# PR9025.net
KiCad netlist of a schematic drawn in EAGLE
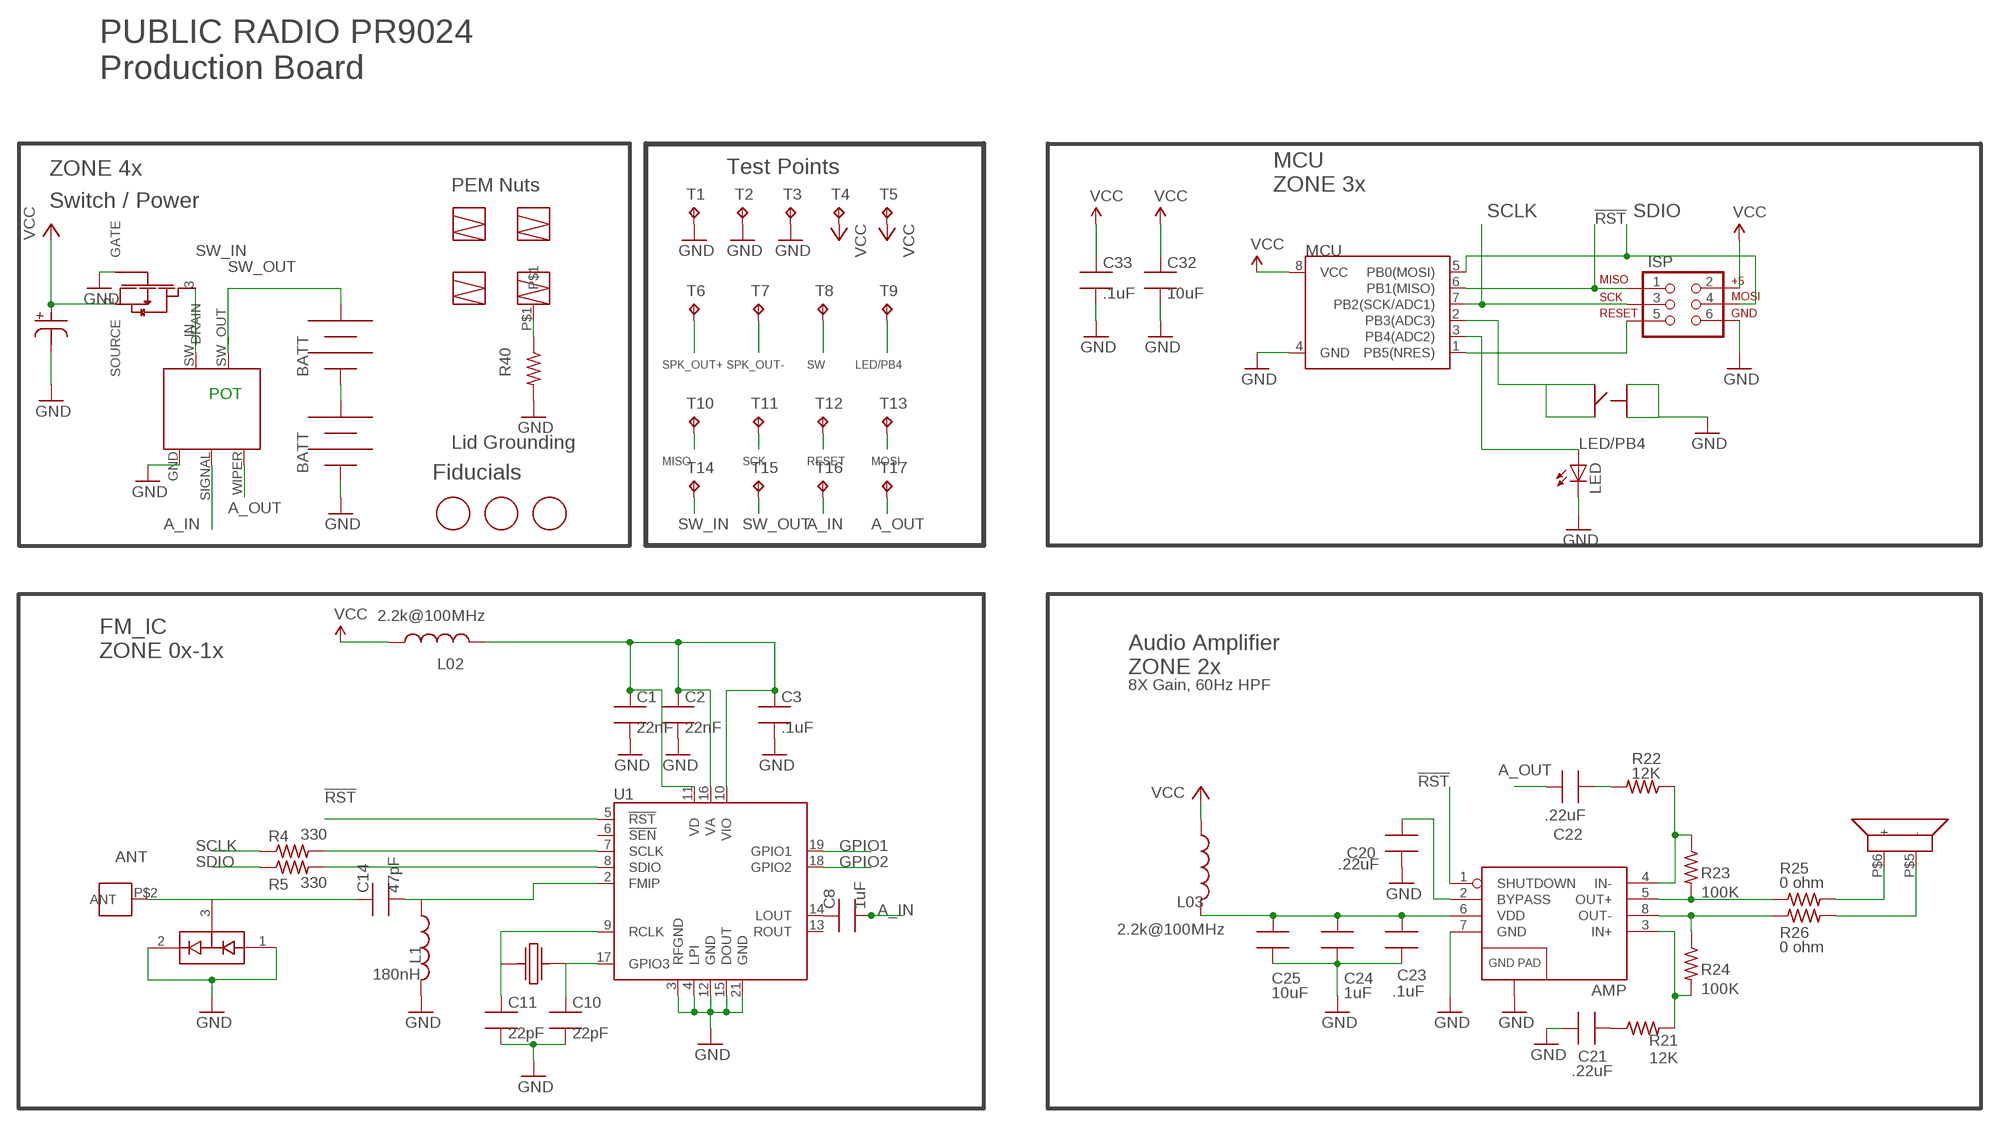
[diagram p0: schematic, sheet 1]

(export (version "E")
  (design (tool "Eeschema 10.0.6"))
  (components
    (comp (ref "AMP")
      (value "TPA6203A1")
      (footprint "eagle-import:8-MSOP")
      (libsource (lib "eagle-import") (part "TPA6203A1"))
    )
    (comp (ref "ANT_MOUNT")
      (value "DNP")
      (footprint "eagle-import:PEM_M3")
      (libsource (lib "eagle-import") (part "M3_PEMNUT"))
    )
    (comp (ref "C1")
      (value "22nF")
      (footprint "eagle-import:0603_CPL")
      (fields
        (field (name "MFG_PN") "CL10B223KB8NNNC")
        (field (name "TOL") "10%")
        (field (name "VOLTAGE") "16V")
      )
      (libsource (lib "eagle-import") (part "C_SMT_0603_CPL"))
    )
    (comp (ref "C2")
      (value "22nF")
      (footprint "eagle-import:0603_CPL")
      (fields
        (field (name "MFG_PN") "CL10B223KB8NNNC")
        (field (name "TOL") "10%")
        (field (name "VOLTAGE") "16V")
      )
      (libsource (lib "eagle-import") (part "C_SMT_0603_CPL"))
    )
    (comp (ref "C3")
      (value ".1uF")
      (footprint "eagle-import:0603_CPL")
      (fields
        (field (name "MFG_PN") "CL10B104KB8SFNC")
        (field (name "TOL") "10%")
        (field (name "VOLTAGE") "16V")
      )
      (libsource (lib "eagle-import") (part "C_SMT_0603_CPL"))
    )
    (comp (ref "C8")
      (value "1uF")
      (footprint "eagle-import:0603_CPL")
      (fields
        (field (name "MFG_PN") "CL10B105KP8NNNC")
        (field (name "TOL") "10%")
        (field (name "VOLTAGE") "10V")
      )
      (libsource (lib "eagle-import") (part "C_SMT_0603_CPL"))
    )
    (comp (ref "C10")
      (value "22pF")
      (footprint "eagle-import:0603_CPL")
      (fields
        (field (name "MFG_PN") "C1608C0G1H220J080AA")
        (field (name "TOL") "5%")
        (field (name "VOLTAGE") "50V")
      )
      (libsource (lib "eagle-import") (part "C_SMT_0603_CPL"))
    )
    (comp (ref "C11")
      (value "22pF")
      (footprint "eagle-import:0603_CPL")
      (fields
        (field (name "MFG_PN") "C1608C0G1H220J080AA")
        (field (name "TOL") "5%")
        (field (name "VOLTAGE") "50V")
      )
      (libsource (lib "eagle-import") (part "C_SMT_0603_CPL"))
    )
    (comp (ref "C14")
      (value "47pF")
      (footprint "eagle-import:0603_CPL")
      (fields
        (field (name "MFG_PN") "CL10C470JB8NCNC")
        (field (name "TOL") "5%")
        (field (name "VOLTAGE") "50V")
      )
      (libsource (lib "eagle-import") (part "C_SMT_0603_CPL"))
    )
    (comp (ref "C20")
      (value ".22uF")
      (footprint "eagle-import:0603_CPL")
      (fields
        (field (name "MFG_PN") "C1608X7R1C224K080AC")
        (field (name "TOL") "10%")
        (field (name "VOLTAGE") "16V")
      )
      (libsource (lib "eagle-import") (part "C_SMT_0603_CPL"))
    )
    (comp (ref "C21")
      (value ".22uF")
      (footprint "eagle-import:0603_CPL")
      (fields
        (field (name "MFG_PN") "C1608X7R1C224K080AC")
        (field (name "TOL") "10%")
        (field (name "VOLTAGE") "16V")
      )
      (libsource (lib "eagle-import") (part "C_SMT_0603_CPL"))
    )
    (comp (ref "C22")
      (value ".22uF")
      (footprint "eagle-import:0603_CPL")
      (fields
        (field (name "MFG_PN") "C1608X7R1C224K080AC")
        (field (name "TOL") "10%")
        (field (name "VOLTAGE") "16V")
      )
      (libsource (lib "eagle-import") (part "C_SMT_0603_CPL"))
    )
    (comp (ref "C23")
      (value ".1uF")
      (footprint "eagle-import:0603_CPL")
      (fields
        (field (name "MFG_PN") "CL10B104KB8SFNC")
        (field (name "TOL") "10%")
        (field (name "VOLTAGE") "16V")
      )
      (libsource (lib "eagle-import") (part "C_SMT_0603_CPL"))
    )
    (comp (ref "C24")
      (value "1uF")
      (footprint "eagle-import:0603_CPL")
      (fields
        (field (name "MFG_PN") "CL10B105KP8NNNC")
        (field (name "TOL") "10%")
        (field (name "VOLTAGE") "10V")
      )
      (libsource (lib "eagle-import") (part "C_SMT_0603_CPL"))
    )
    (comp (ref "C25")
      (value "10uF")
      (footprint "eagle-import:0603_CPL")
      (fields
        (field (name "MFG_PN") "CL10A106MQ8NNNC")
        (field (name "TOL") "20%")
        (field (name "VOLTAGE") "6.3V")
      )
      (libsource (lib "eagle-import") (part "C_SMT_0603_CPL"))
    )
    (comp (ref "C32")
      (value "10uF")
      (footprint "eagle-import:0603_CPL")
      (fields
        (field (name "MFG_PN") "CL10A106MQ8NNNC")
        (field (name "TOL") "20%")
        (field (name "VOLTAGE") "6.3V")
      )
      (libsource (lib "eagle-import") (part "C_SMT_0603_CPL"))
    )
    (comp (ref "C33")
      (value ".1uF")
      (footprint "eagle-import:0603_CPL")
      (fields
        (field (name "MFG_PN") "CL10B104KB8SFNC")
        (field (name "TOL") "10%")
        (field (name "VOLTAGE") "16V")
      )
      (libsource (lib "eagle-import") (part "C_SMT_0603_CPL"))
    )
    (comp (ref "C40")
      (value "220uF")
      (footprint "eagle-import:NICHICON_UD_63")
      (fields (field (name "TOL") "20%") (field (name "VOLTAGE") "16V"))
      (libsource (lib "eagle-import") (part "NICHICON_SERIESUD"))
    )
    (comp (ref "D1")
      (value "BAV99")
      (footprint "eagle-import:SOT23_CPL")
      (fields (field (name "MFG_PN") "BAV99,215"))
      (libsource (lib "eagle-import") (part "BAV99"))
    )
    (comp (ref "FET1")
      (value "AO3435")
      (footprint "eagle-import:SOT23_CPL")
      (fields (field (name "MFG_PN") "AO3435"))
      (libsource (lib "eagle-import") (part "AO3435"))
    )
    (comp (ref "ISP")
      (value "AVR_SPI_PRG_6NS")
      (footprint "eagle-import:2X3-NS")
      (libsource (lib "eagle-import") (part "AVR_SPI_PRG_6NS"))
    )
    (comp (ref "JP5")
      (value "BK-92_MPD_AA_BATT_CLIP")
      (footprint "eagle-import:BK92_AA_BATT")
      (fields (field (name "MFG_PN") "2 of BK92 - supplied by CL Labs"))
      (libsource (lib "eagle-import") (part "BK-92_MPD_AA_BATT_CLIP"))
    )
    (comp (ref "JP6")
      (value "BK-92_MPD_AA_BATT_CLIP")
      (footprint "eagle-import:BK92_AA_BATT")
      (fields (field (name "MFG_PN") "2 of BK92 - supplied by CL Labs"))
      (libsource (lib "eagle-import") (part "BK-92_MPD_AA_BATT_CLIP"))
    )
    (comp (ref "L1")
      (value "180nH")
      (footprint "eagle-import:0805_ADAFRUIT")
      (fields
        (field (name "CURRENT") "400mA")
        (field (name "DCR") "640m")
        (field (name "MFG_PN") "AISC-0805-R18J-T")
        (field (name "TOL") "5%")
      )
      (libsource (lib "eagle-import") (part "L_SMT_0805_ADAFRUIT"))
    )
    (comp (ref "L02")
      (value "2.2k@100MHz")
      (footprint "eagle-import:0603_CPL")
      (fields
        (field (name "CURRENT") "150mA")
        (field (name "DCR") "2.3")
        (field (name "MFG_PN") "HZ0603A222R-10")
      )
      (libsource (lib "eagle-import") (part "L_SMT_0603_CPL"))
    )
    (comp (ref "L03")
      (value "2.2k@100MHz")
      (footprint "eagle-import:0603_CPL")
      (fields
        (field (name "CURRENT") "150mA")
        (field (name "DCR") "2.3")
        (field (name "MFG_PN") "HZ0603A222R-10")
      )
      (libsource (lib "eagle-import") (part "L_SMT_0603_CPL"))
    )
    (comp (ref "LED")
      (value "HSMC-C265_REVERSE_MOUNT_LED")
      (footprint "eagle-import:HSMC-C265_REVERSE_MOUN_LED")
      (libsource (lib "eagle-import") (part "HSMC-C265_REVERSE_MOUNT_LED"))
    )
    (comp (ref "MARK1")
      (value "FIDUCIAL")
      (footprint "eagle-import:FIDUCIAL_1MM")
      (libsource (lib "eagle-import") (part "FIDUCIAL"))
    )
    (comp (ref "MARK2")
      (value "FIDUCIAL")
      (footprint "eagle-import:FIDUCIAL_1MM")
      (libsource (lib "eagle-import") (part "FIDUCIAL"))
    )
    (comp (ref "MARK3")
      (value "FIDUCIAL")
      (footprint "eagle-import:FIDUCIAL_1MM")
      (libsource (lib "eagle-import") (part "FIDUCIAL"))
    )
    (comp (ref "MCU")
      (value "ATTINY45TINY45-20-SMT")
      (footprint "eagle-import:8-SOIC")
      (libsource (lib "eagle-import") (part "ATTINY45TINY45-20-SMT"))
    )
    (comp (ref "R1")
      (value "VOLUME_POT")
      (footprint "eagle-import:H17112NS_A10K_L20F-002")
      (libsource (lib "eagle-import") (part "VOLUME_POT"))
    )
    (comp (ref "R4")
      (value "330")
      (footprint "eagle-import:0603_CPL")
      (fields (field (name "MFG_PN") "MCR03ERTJ331") (field (name "POWER") "1/10W") (field (name "TOL") "5%"))
      (libsource (lib "eagle-import") (part "R_SMT_R0603_CPL"))
    )
    (comp (ref "R5")
      (value "330")
      (footprint "eagle-import:0603_CPL")
      (fields (field (name "MFG_PN") "MCR03ERTJ331") (field (name "POWER") "1/10W") (field (name "TOL") "5%"))
      (libsource (lib "eagle-import") (part "R_SMT_R0603_CPL"))
    )
    (comp (ref "R21")
      (value "12K")
      (footprint "eagle-import:0603_CPL")
      (fields
        (field (name "MFG_PN") "RC0603FR-0712KL")
        (field (name "POWER") "1/10W")
        (field (name "TOL") "1%")
      )
      (libsource (lib "eagle-import") (part "R_SMT_R0603_CPL"))
    )
    (comp (ref "R22")
      (value "12K")
      (footprint "eagle-import:0603_CPL")
      (fields
        (field (name "MFG_PN") "RC0603FR-0712KL")
        (field (name "POWER") "1/10W")
        (field (name "TOL") "1%")
      )
      (libsource (lib "eagle-import") (part "R_SMT_R0603_CPL"))
    )
    (comp (ref "R23")
      (value "100K")
      (footprint "eagle-import:0603_CPL")
      (fields
        (field (name "MFG_PN") "ERJ-3EKF1003V")
        (field (name "POWER") "1/10W")
        (field (name "TOL") "1%")
      )
      (libsource (lib "eagle-import") (part "R_SMT_R0603_CPL"))
    )
    (comp (ref "R24")
      (value "100K")
      (footprint "eagle-import:0603_CPL")
      (fields
        (field (name "MFG_PN") "ERJ-3EKF1003V")
        (field (name "POWER") "1/10W")
        (field (name "TOL") "1%")
      )
      (libsource (lib "eagle-import") (part "R_SMT_R0603_CPL"))
    )
    (comp (ref "R25")
      (value "0 ohm")
      (footprint "eagle-import:0805_ADAFRUIT")
      (fields (field (name "MFG_PN") "ERJ-6GEY0R00V "))
      (libsource (lib "eagle-import") (part "R_SMT_0805_ADAFRUIT"))
    )
    (comp (ref "R26")
      (value "0 ohm")
      (footprint "eagle-import:0805_ADAFRUIT")
      (fields (field (name "MFG_PN") "ERJ-6GEY0R00V "))
      (libsource (lib "eagle-import") (part "R_SMT_0805_ADAFRUIT"))
    )
    (comp (ref "R40")
      (value "DNP")
      (footprint "eagle-import:0603_CPL")
      (fields (field (name "MFG_PN") "ERJ-3GEY0R00V"))
      (libsource (lib "eagle-import") (part "R_SMT_R0603_CPL"))
    )
    (comp (ref "SPKR_PLACE")
      (value "DNP")
      (footprint "eagle-import:PR2024_SPKR_PLACE(SMD)")
      (libsource (lib "eagle-import") (part "PR2024_SPKR_SMD"))
    )
    (comp (ref "SW1")
      (value "C&K_PTS645")
      (footprint "eagle-import:C&K_PTS645_SMT")
      (libsource (lib "eagle-import") (part "C&K_PTS645"))
    )
    (comp (ref "T1")
      (value "TPTP20R")
      (footprint "eagle-import:TP20R")
      (libsource (lib "eagle-import") (part "TPTP20R"))
    )
    (comp (ref "T2")
      (value "TPTP20R")
      (footprint "eagle-import:TP20R")
      (libsource (lib "eagle-import") (part "TPTP20R"))
    )
    (comp (ref "T3")
      (value "TPTP20R")
      (footprint "eagle-import:TP20R")
      (libsource (lib "eagle-import") (part "TPTP20R"))
    )
    (comp (ref "T4")
      (value "TPTP20R")
      (footprint "eagle-import:TP20R")
      (libsource (lib "eagle-import") (part "TPTP20R"))
    )
    (comp (ref "T5")
      (value "TPTP20R")
      (footprint "eagle-import:TP20R")
      (libsource (lib "eagle-import") (part "TPTP20R"))
    )
    (comp (ref "T6")
      (value "TPTP20R")
      (footprint "eagle-import:TP20R")
      (libsource (lib "eagle-import") (part "TPTP20R"))
    )
    (comp (ref "T7")
      (value "TPTP20R")
      (footprint "eagle-import:TP20R")
      (libsource (lib "eagle-import") (part "TPTP20R"))
    )
    (comp (ref "T8")
      (value "TPTP20R")
      (footprint "eagle-import:TP20R")
      (libsource (lib "eagle-import") (part "TPTP20R"))
    )
    (comp (ref "T9")
      (value "TPTP20R")
      (footprint "eagle-import:TP20R")
      (libsource (lib "eagle-import") (part "TPTP20R"))
    )
    (comp (ref "T10")
      (value "TPTP20R")
      (footprint "eagle-import:TP20R")
      (libsource (lib "eagle-import") (part "TPTP20R"))
    )
    (comp (ref "T11")
      (value "TPTP20R")
      (footprint "eagle-import:TP20R")
      (libsource (lib "eagle-import") (part "TPTP20R"))
    )
    (comp (ref "T12")
      (value "TPTP20R")
      (footprint "eagle-import:TP20R")
      (libsource (lib "eagle-import") (part "TPTP20R"))
    )
    (comp (ref "T13")
      (value "TPTP20R")
      (footprint "eagle-import:TP20R")
      (libsource (lib "eagle-import") (part "TPTP20R"))
    )
    (comp (ref "T14")
      (value "TPTP20R")
      (footprint "eagle-import:TP20R")
      (libsource (lib "eagle-import") (part "TPTP20R"))
    )
    (comp (ref "T15")
      (value "TPTP20R")
      (footprint "eagle-import:TP20R")
      (libsource (lib "eagle-import") (part "TPTP20R"))
    )
    (comp (ref "T16")
      (value "TPTP20R")
      (footprint "eagle-import:TP20R")
      (libsource (lib "eagle-import") (part "TPTP20R"))
    )
    (comp (ref "T17")
      (value "TPTP20R")
      (footprint "eagle-import:TP20R")
      (libsource (lib "eagle-import") (part "TPTP20R"))
    )
    (comp (ref "U$2")
      (value "PEM_SMT")
      (footprint "eagle-import:PEM_SMT")
      (libsource (lib "eagle-import") (part "PEM_SMT"))
    )
    (comp (ref "U$3")
      (value "PEM_SMT")
      (footprint "eagle-import:PEM_SMT")
      (libsource (lib "eagle-import") (part "PEM_SMT"))
    )
    (comp (ref "U$4")
      (value "PEM_SMT")
      (footprint "eagle-import:PEM_SMT")
      (libsource (lib "eagle-import") (part "PEM_SMT"))
    )
    (comp (ref "U$5")
      (value "PEM_M3_SMT_W/PIN")
      (footprint "eagle-import:PEM_SMT")
      (libsource (lib "eagle-import") (part "PEM_M3_SMT_W/PIN"))
    )
    (comp (ref "U1")
      (value "SI4702-C19-GMR")
      (footprint "eagle-import:SI470X_20_QFN")
      (fields (field (name "MFG_PN") "Si4702 C19 GM - supplied by CL Labs"))
      (libsource (lib "eagle-import") (part "SI4702-C19-GMR"))
    )
    (comp (ref "X1")
      (value "ABS25XTAL")
      (footprint "eagle-import:4-SOJ")
      (libsource (lib "eagle-import") (part "ABS25XTAL"))
    )
  )
  (nets
    (net (code "1") (name "/ANT") (class "Default")
      (node (ref "ANT_MOUNT") (pin "P$2") (pinfunction "ANT_P$2") (pintype "bidirectional"))
      (node (ref "C14") (pin "1") (pinfunction "1_1") (pintype "passive"))
      (node (ref "D1") (pin "3") (pinfunction "COM_3") (pintype "bidirectional"))
    )
    (net (code "2") (name "/A_IN") (class "Default")
      (node (ref "C8") (pin "2") (pinfunction "2_2") (pintype "passive"))
      (node (ref "R1") (pin "SIGNAL") (pinfunction "SIGNAL_SIGNAL") (pintype "bidirectional"))
      (node (ref "T16") (pin "TP") (pinfunction "TP_TP") (pintype "input"))
    )
    (net (code "3") (name "/A_OUT") (class "Default")
      (node (ref "C22") (pin "2") (pinfunction "2_2") (pintype "passive"))
      (node (ref "R1") (pin "WIPER") (pinfunction "WIPER_WIPER") (pintype "bidirectional"))
      (node (ref "T17") (pin "TP") (pinfunction "TP_TP") (pintype "input"))
    )
    (net (code "4") (name "/GPIO1") (class "Default")
      (node (ref "U1") (pin "19") (pinfunction "GPIO1_19") (pintype "bidirectional"))
    )
    (net (code "5") (name "/GPIO2") (class "Default")
      (node (ref "U1") (pin "18") (pinfunction "GPIO2_18") (pintype "bidirectional"))
    )
    (net (code "6") (name "/LED{slash}PB4") (class "Default")
      (node (ref "LED") (pin "P$1") (pinfunction "A_P$1") (pintype "passive"))
      (node (ref "MCU") (pin "3") (pinfunction "PB4(ADC2)_3") (pintype "bidirectional"))
      (node (ref "T9") (pin "TP") (pinfunction "TP_TP") (pintype "input"))
    )
    (net (code "7") (name "/RESET") (class "Default")
      (node (ref "ISP") (pin "5") (pinfunction "5_5") (pintype "passive"))
      (node (ref "MCU") (pin "1") (pinfunction "PB5(NRES)_1") (pintype "bidirectional"))
      (node (ref "T12") (pin "TP") (pinfunction "TP_TP") (pintype "input"))
    )
    (net (code "8") (name "/SCLK") (class "Default")
      (node (ref "ISP") (pin "3") (pinfunction "3_3") (pintype "passive"))
      (node (ref "MCU") (pin "7") (pinfunction "PB2(SCK/ADC1)_7") (pintype "bidirectional"))
      (node (ref "R4") (pin "1") (pinfunction "1_1") (pintype "passive"))
      (node (ref "T11") (pin "TP") (pinfunction "TP_TP") (pintype "input"))
    )
    (net (code "9") (name "/SDIO") (class "Default")
      (node (ref "ISP") (pin "4") (pinfunction "4_4") (pintype "passive"))
      (node (ref "MCU") (pin "5") (pinfunction "PB0(MOSI)_5") (pintype "bidirectional"))
      (node (ref "R5") (pin "1") (pinfunction "1_1") (pintype "passive"))
      (node (ref "T13") (pin "TP") (pinfunction "TP_TP") (pintype "input"))
    )
    (net (code "10") (name "/SPK_OUT+") (class "Default")
      (node (ref "R25") (pin "2") (pinfunction "2_2") (pintype "passive"))
      (node (ref "SPKR_PLACE") (pin "P$6") (pinfunction "+_P$6") (pintype "bidirectional"))
      (node (ref "T6") (pin "TP") (pinfunction "TP_TP") (pintype "input"))
    )
    (net (code "11") (name "/SPK_OUT-") (class "Default")
      (node (ref "R26") (pin "2") (pinfunction "2_2") (pintype "passive"))
      (node (ref "SPKR_PLACE") (pin "P$5") (pinfunction "-_P$5") (pintype "bidirectional"))
      (node (ref "T7") (pin "TP") (pinfunction "TP_TP") (pintype "input"))
    )
    (net (code "12") (name "/SW") (class "Default")
      (node (ref "MCU") (pin "2") (pinfunction "PB3(ADC3)_2") (pintype "bidirectional"))
      (node (ref "SW1") (pin "P$3") (pinfunction "P$3_P$3") (pintype "bidirectional"))
      (node (ref "SW1") (pin "P$4") (pinfunction "P$4_P$4") (pintype "bidirectional"))
      (node (ref "T8") (pin "TP") (pinfunction "TP_TP") (pintype "input"))
    )
    (net (code "13") (name "/SW_IN") (class "Default")
      (node (ref "FET1") (pin "3") (pinfunction "DRAIN_3") (pintype "bidirectional"))
      (node (ref "R1") (pin "SW_IN") (pinfunction "SW_IN_SW_IN") (pintype "bidirectional"))
      (node (ref "T14") (pin "TP") (pinfunction "TP_TP") (pintype "input"))
    )
    (net (code "14") (name "/SW_OUT") (class "Default")
      (node (ref "JP5") (pin "POS") (pinfunction "POS_POS") (pintype "bidirectional"))
      (node (ref "JP5") (pin "POS@2") (pinfunction "POS_POS@2") (pintype "bidirectional"))
      (node (ref "R1") (pin "SW_OUT") (pinfunction "SW_OUT_SW_OUT") (pintype "bidirectional"))
      (node (ref "T15") (pin "TP") (pinfunction "TP_TP") (pintype "input"))
    )
    (net (code "15") (name "/~{RST}") (class "Default")
      (node (ref "AMP") (pin "1") (pinfunction "SHUTDOWN_1") (pintype "input"))
      (node (ref "ISP") (pin "1") (pinfunction "1_1") (pintype "passive"))
      (node (ref "MCU") (pin "6") (pinfunction "PB1(MISO)_6") (pintype "bidirectional"))
      (node (ref "T10") (pin "TP") (pinfunction "TP_TP") (pintype "input"))
      (node (ref "U1") (pin "5") (pinfunction "~{RST}_5") (pintype "bidirectional"))
    )
    (net (code "16") (name "GND") (class "Default")
      (node (ref "AMP") (pin "7") (pinfunction "GND_7") (pintype "power_in"))
      (node (ref "AMP") (pin "9") (pinfunction "GND_9") (pintype "power_in"))
      (node (ref "C1") (pin "2") (pinfunction "2_2") (pintype "passive"))
      (node (ref "C10") (pin "2") (pinfunction "2_2") (pintype "passive"))
      (node (ref "C11") (pin "2") (pinfunction "2_2") (pintype "passive"))
      (node (ref "C2") (pin "2") (pinfunction "2_2") (pintype "passive"))
      (node (ref "C20") (pin "1") (pinfunction "1_1") (pintype "passive"))
      (node (ref "C21") (pin "1") (pinfunction "1_1") (pintype "passive"))
      (node (ref "C23") (pin "2") (pinfunction "2_2") (pintype "passive"))
      (node (ref "C24") (pin "2") (pinfunction "2_2") (pintype "passive"))
      (node (ref "C25") (pin "2") (pinfunction "2_2") (pintype "passive"))
      (node (ref "C3") (pin "2") (pinfunction "2_2") (pintype "passive"))
      (node (ref "C32") (pin "2") (pinfunction "2_2") (pintype "passive"))
      (node (ref "C33") (pin "2") (pinfunction "2_2") (pintype "passive"))
      (node (ref "C40") (pin "P$2") (pinfunction "P$2_P$2") (pintype "bidirectional"))
      (node (ref "D1") (pin "1") (pinfunction "A1_1") (pintype "bidirectional"))
      (node (ref "D1") (pin "2") (pinfunction "C2_2") (pintype "bidirectional"))
      (node (ref "FET1") (pin "1") (pinfunction "GATE_1") (pintype "bidirectional"))
      (node (ref "ISP") (pin "6") (pinfunction "6_6") (pintype "passive"))
      (node (ref "JP6") (pin "NEG") (pinfunction "NEG_NEG") (pintype "bidirectional"))
      (node (ref "JP6") (pin "NEG@2") (pinfunction "NEG_NEG@2") (pintype "bidirectional"))
      (node (ref "L1") (pin "2") (pinfunction "2_2") (pintype "passive"))
      (node (ref "LED") (pin "P$2") (pinfunction "C_P$2") (pintype "passive"))
      (node (ref "MCU") (pin "4") (pinfunction "GND_4") (pintype "bidirectional"))
      (node (ref "R1") (pin "GND") (pinfunction "GND_GND") (pintype "bidirectional"))
      (node (ref "R40") (pin "2") (pinfunction "2_2") (pintype "passive"))
      (node (ref "SW1") (pin "P$1") (pinfunction "P$1_P$1") (pintype "bidirectional"))
      (node (ref "SW1") (pin "P$2") (pinfunction "P$2_P$2") (pintype "bidirectional"))
      (node (ref "T1") (pin "TP") (pinfunction "TP_TP") (pintype "input"))
      (node (ref "T2") (pin "TP") (pinfunction "TP_TP") (pintype "input"))
      (node (ref "T3") (pin "TP") (pinfunction "TP_TP") (pintype "input"))
      (node (ref "U1") (pin "12") (pinfunction "GND_12") (pintype "bidirectional"))
      (node (ref "U1") (pin "15") (pinfunction "DOUT_15") (pintype "bidirectional"))
      (node (ref "U1") (pin "21") (pinfunction "GND_21") (pintype "bidirectional"))
      (node (ref "U1") (pin "3") (pinfunction "RFGND_3") (pintype "bidirectional"))
      (node (ref "U1") (pin "4") (pinfunction "LPI_4") (pintype "bidirectional"))
    )
    (net (code "17") (name "Net-(AMP-BYPASS)") (class "Default")
      (node (ref "AMP") (pin "2") (pinfunction "BYPASS_2") (pintype "bidirectional"))
      (node (ref "C20") (pin "2") (pinfunction "2_2") (pintype "passive"))
    )
    (net (code "18") (name "Net-(AMP-IN+)") (class "Default")
      (node (ref "AMP") (pin "3") (pinfunction "IN+_3") (pintype "bidirectional"))
      (node (ref "R21") (pin "2") (pinfunction "2_2") (pintype "passive"))
      (node (ref "R24") (pin "2") (pinfunction "2_2") (pintype "passive"))
    )
    (net (code "19") (name "Net-(AMP-IN-)") (class "Default")
      (node (ref "AMP") (pin "4") (pinfunction "IN-_4") (pintype "bidirectional"))
      (node (ref "R22") (pin "1") (pinfunction "1_1") (pintype "passive"))
      (node (ref "R23") (pin "1") (pinfunction "1_1") (pintype "passive"))
    )
    (net (code "20") (name "Net-(AMP-OUT+)") (class "Default")
      (node (ref "AMP") (pin "5") (pinfunction "OUT+_5") (pintype "bidirectional"))
      (node (ref "R23") (pin "2") (pinfunction "2_2") (pintype "passive"))
      (node (ref "R25") (pin "1") (pinfunction "1_1") (pintype "passive"))
    )
    (net (code "21") (name "Net-(AMP-OUT-)") (class "Default")
      (node (ref "AMP") (pin "8") (pinfunction "OUT-_8") (pintype "bidirectional"))
      (node (ref "R24") (pin "1") (pinfunction "1_1") (pintype "passive"))
      (node (ref "R26") (pin "1") (pinfunction "1_1") (pintype "passive"))
    )
    (net (code "22") (name "Net-(AMP-VDD)") (class "Default")
      (node (ref "AMP") (pin "6") (pinfunction "VDD_6") (pintype "power_in"))
      (node (ref "C23") (pin "1") (pinfunction "1_1") (pintype "passive"))
      (node (ref "C24") (pin "1") (pinfunction "1_1") (pintype "passive"))
      (node (ref "C25") (pin "1") (pinfunction "1_1") (pintype "passive"))
      (node (ref "L03") (pin "2") (pinfunction "2_2") (pintype "passive"))
    )
    (net (code "23") (name "Net-(C21-Pad2)") (class "Default")
      (node (ref "C21") (pin "2") (pinfunction "2_2") (pintype "passive"))
      (node (ref "R21") (pin "1") (pinfunction "1_1") (pintype "passive"))
    )
    (net (code "24") (name "Net-(C22-Pad1)") (class "Default")
      (node (ref "C22") (pin "1") (pinfunction "1_1") (pintype "passive"))
      (node (ref "R22") (pin "2") (pinfunction "2_2") (pintype "passive"))
    )
    (net (code "25") (name "Net-(JP5-NEG-PadNEG@2)") (class "Default")
      (node (ref "JP5") (pin "NEG") (pinfunction "NEG_NEG") (pintype "bidirectional"))
      (node (ref "JP5") (pin "NEG@2") (pinfunction "NEG_NEG@2") (pintype "bidirectional"))
      (node (ref "JP6") (pin "POS") (pinfunction "POS_POS") (pintype "bidirectional"))
      (node (ref "JP6") (pin "POS@2") (pinfunction "POS_POS@2") (pintype "bidirectional"))
    )
    (net (code "26") (name "Net-(R40-Pad1)") (class "Default")
      (node (ref "R40") (pin "1") (pinfunction "1_1") (pintype "passive"))
      (node (ref "U$5") (pin "P$1") (pinfunction "P$1_P$1") (pintype "bidirectional"))
    )
    (net (code "27") (name "Net-(U1-FMIP)") (class "Default")
      (node (ref "C14") (pin "2") (pinfunction "2_2") (pintype "passive"))
      (node (ref "L1") (pin "1") (pinfunction "1_1") (pintype "passive"))
      (node (ref "U1") (pin "2") (pinfunction "FMIP_2") (pintype "bidirectional"))
    )
    (net (code "28") (name "Net-(U1-GPIO3)") (class "Default")
      (node (ref "C10") (pin "1") (pinfunction "1_1") (pintype "passive"))
      (node (ref "U1") (pin "17") (pinfunction "GPIO3_17") (pintype "bidirectional"))
      (node (ref "X1") (pin "P$4") (pinfunction "P$4_P$4") (pintype "bidirectional"))
    )
    (net (code "29") (name "Net-(U1-LOUT)") (class "Default")
      (node (ref "C8") (pin "1") (pinfunction "1_1") (pintype "passive"))
      (node (ref "U1") (pin "14") (pinfunction "LOUT_14") (pintype "bidirectional"))
    )
    (net (code "30") (name "Net-(U1-RCLK)") (class "Default")
      (node (ref "C11") (pin "1") (pinfunction "1_1") (pintype "passive"))
      (node (ref "U1") (pin "9") (pinfunction "RCLK_9") (pintype "bidirectional"))
      (node (ref "X1") (pin "P$1") (pinfunction "P$1_P$1") (pintype "bidirectional"))
    )
    (net (code "31") (name "Net-(U1-SCLK)") (class "Default")
      (node (ref "R4") (pin "2") (pinfunction "2_2") (pintype "passive"))
      (node (ref "U1") (pin "7") (pinfunction "SCLK_7") (pintype "bidirectional"))
    )
    (net (code "32") (name "Net-(U1-SDIO)") (class "Default")
      (node (ref "R5") (pin "2") (pinfunction "2_2") (pintype "passive"))
      (node (ref "U1") (pin "8") (pinfunction "SDIO_8") (pintype "bidirectional"))
    )
    (net (code "33") (name "Net-(U1-VA)") (class "Default")
      (node (ref "C1") (pin "1") (pinfunction "1_1") (pintype "passive"))
      (node (ref "C2") (pin "1") (pinfunction "1_1") (pintype "passive"))
      (node (ref "C3") (pin "1") (pinfunction "1_1") (pintype "passive"))
      (node (ref "L02") (pin "2") (pinfunction "2_2") (pintype "passive"))
      (node (ref "U1") (pin "10") (pinfunction "VIO_10") (pintype "bidirectional"))
      (node (ref "U1") (pin "11") (pinfunction "VD_11") (pintype "bidirectional"))
      (node (ref "U1") (pin "16") (pinfunction "VA_16") (pintype "bidirectional"))
    )
    (net (code "34") (name "VCC") (class "Default")
      (node (ref "C32") (pin "1") (pinfunction "1_1") (pintype "passive"))
      (node (ref "C33") (pin "1") (pinfunction "1_1") (pintype "passive"))
      (node (ref "C40") (pin "P$1") (pinfunction "P$1_P$1") (pintype "bidirectional"))
      (node (ref "FET1") (pin "2") (pinfunction "SOURCE_2") (pintype "bidirectional"))
      (node (ref "ISP") (pin "2") (pinfunction "2_2") (pintype "passive"))
      (node (ref "L02") (pin "1") (pinfunction "1_1") (pintype "passive"))
      (node (ref "L03") (pin "1") (pinfunction "1_1") (pintype "passive"))
      (node (ref "MCU") (pin "8") (pinfunction "VCC_8") (pintype "bidirectional"))
      (node (ref "T4") (pin "TP") (pinfunction "TP_TP") (pintype "input"))
      (node (ref "T5") (pin "TP") (pinfunction "TP_TP") (pintype "input"))
    )
    (net (code "35") (name "unconnected-(U1-ROUT-Pad13)") (class "Default")
      (node (ref "U1") (pin "13") (pinfunction "ROUT_13") (pintype "bidirectional"))
    )
    (net (code "36") (name "unconnected-(U1-~{SEN}-Pad6)") (class "Default")
      (node (ref "U1") (pin "6") (pinfunction "~{SEN}_6") (pintype "bidirectional"))
    )
  )
)
